# USB_UART.net
KiCad netlist of a schematic drawn in Altium Designer
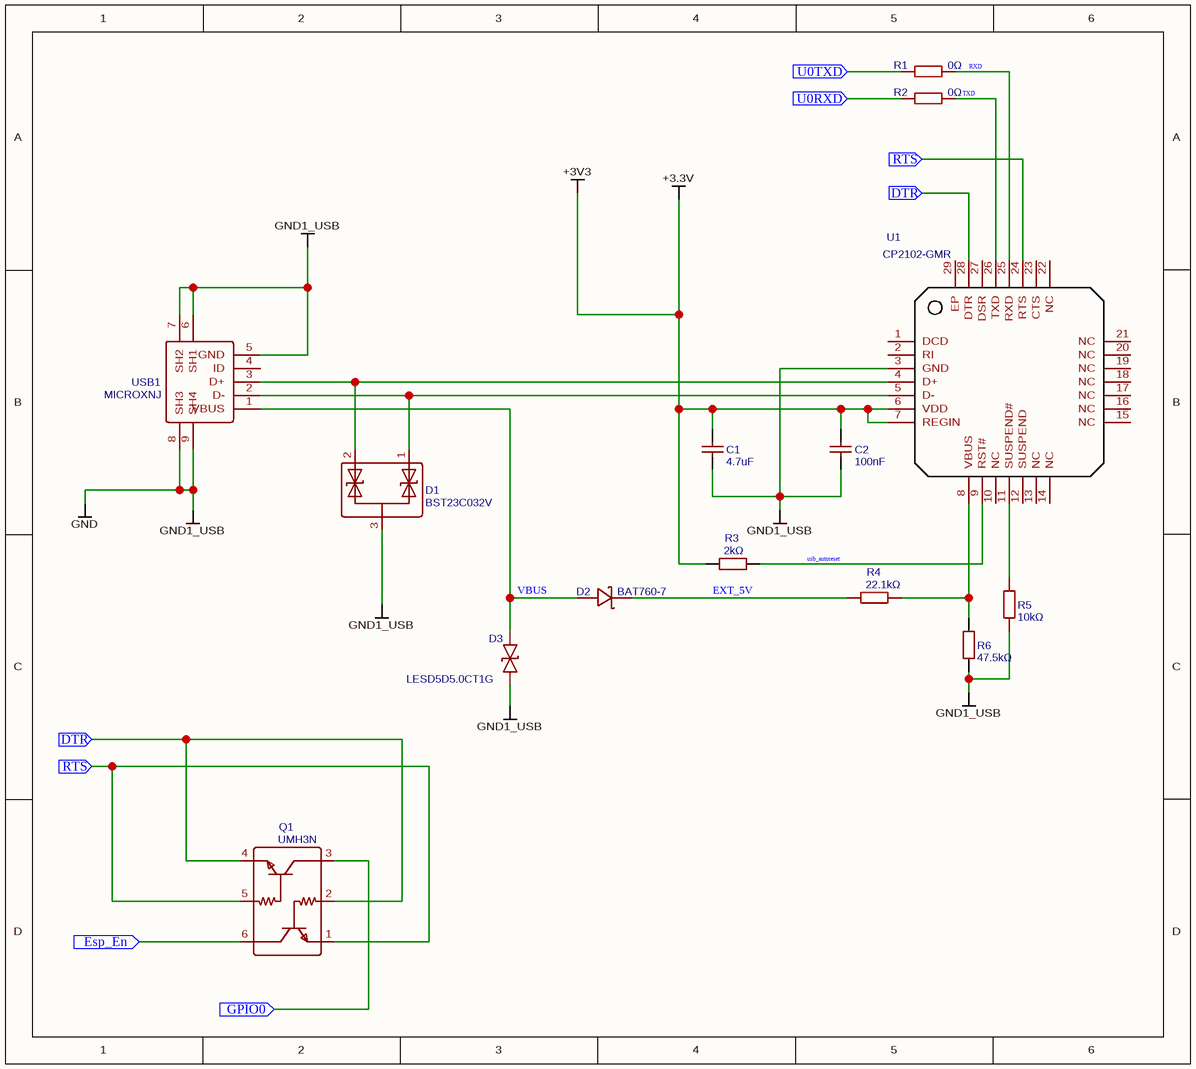
[diagram p0: USB_UART.schdoc]

(export (version "E")
  (design (tool "Eeschema 10.0.6"))
  (components
    (comp (ref "C1")
      (value "4.7uF")
      (fields
        (field (name "BOM_MANUFACTURER PART") "0603X475K160NT")
        (field (name "BOM_SUPPLIER PART") "C99229")
      )
      (libsource (lib "altium-import") (part "root_1_4.7uF_"))
    )
    (comp (ref "C2")
      (value "100nF")
      (fields
        (field (name "BOM_MANUFACTURER PART") "CL10B104KO8NNNC")
        (field (name "BOM_SUPPLIER PART") "C66501")
      )
      (libsource (lib "altium-import") (part "root_1_100nF_"))
    )
    (comp (ref "D1")
      (value "BST23C032V")
      (fields (field (name "BOM_SUPPLIER PART") "C151968") (field (name "CONTRIBUTOR") "LCSC"))
      (libsource (lib "altium-import") (part "root_2_BST23C032V_"))
    )
    (comp (ref "D2")
      (value "BAT760-7")
      (fields (field (name "BOM_SUPPLIER PART") "C124187") (field (name "CONTRIBUTOR") "LCSC"))
      (libsource (lib "altium-import") (part "root_2_BAT760-7_"))
    )
    (comp (ref "D3")
      (value "LESD5D5.0CT1G")
      (fields (field (name "BOM_SUPPLIER PART") "C383211") (field (name "CONTRIBUTOR") "LCSC"))
      (libsource (lib "altium-import") (part "root_1_LESD5D5.0CT1G_"))
    )
    (comp (ref "Q1")
      (value "UMH3N")
      (fields (field (name "BOM_SUPPLIER PART") "C62892"))
      (libsource (lib "altium-import") (part "root_1_UMH3N_"))
    )
    (comp (ref "R1")
      (value "0Ω")
      (fields
        (field (name "BOM_MANUFACTURER PART") "RS-03000FT")
        (field (name "BOM_SUPPLIER PART") "C136582")
        (field (name "CONTRIBUTOR") "LCSC")
      )
      (libsource (lib "altium-import") (part "root_0_0Ω_"))
    )
    (comp (ref "R2")
      (value "0Ω")
      (fields
        (field (name "BOM_MANUFACTURER PART") "RS-03000FT")
        (field (name "BOM_SUPPLIER PART") "C136582")
        (field (name "CONTRIBUTOR") "LCSC")
      )
      (libsource (lib "altium-import") (part "root_0_0Ω_"))
    )
    (comp (ref "R3")
      (value "2kΩ")
      (fields
        (field (name "BOM_MANUFACTURER PART") "RS-03K2001FT")
        (field (name "BOM_SUPPLIER PART") "C115336")
      )
      (libsource (lib "altium-import") (part "root_0_2kΩ_"))
    )
    (comp (ref "R4")
      (value "22.1kΩ")
      (fields
        (field (name "BOM_SUPPLIER PART") "C310274")
        (field (name "BOM_MANUFACTURER PART") "RS-03K2212FT")
        (field (name "CONTRIBUTOR") "LCSC")
      )
      (libsource (lib "altium-import") (part "root_0_22.1kΩ_"))
    )
    (comp (ref "R5")
      (value "10kΩ")
      (fields
        (field (name "BOM_SUPPLIER PART") "C115324")
        (field (name "BOM_MANUFACTURER PART") "RS-03K1002FT")
        (field (name "CONTRIBUTOR") "LCSC")
      )
      (libsource (lib "altium-import") (part "root_1_10kΩ_"))
    )
    (comp (ref "R6")
      (value "47.5kΩ")
      (fields
        (field (name "BOM_MANUFACTURER PART") "0603WAF4752T5E")
        (field (name "BOM_SUPPLIER PART") "C23061")
      )
      (libsource (lib "altium-import") (part "root_1_47.5kΩ_"))
    )
    (comp (ref "U1")
      (value "CP2102-GMR")
      (fields (field (name "BOM_SUPPLIER PART") "C6568"))
      (libsource (lib "altium-import") (part "root_0_CP2102-GMR_"))
    )
    (comp (ref "USB1")
      (value "MICROXNJ")
      (fields
        (field (name "BOM_SUPPLIER PART") "C404969")
        (field (name "BOM_MANUFACTURER PART") "MicroXNJ")
        (field (name "CONTRIBUTOR") "LCSC")
      )
      (libsource (lib "altium-import") (part "root_0_MICROXNJ_"))
    )
  )
  (nets
    (net (code "1") (name "+3.3V") (class "Default")
      (node (ref "C1") (pin "2") (pinfunction "2_2") (pintype "passive"))
      (node (ref "C2") (pin "2") (pinfunction "2_2") (pintype "passive"))
      (node (ref "R3") (pin "1") (pinfunction "1_1") (pintype "passive"))
      (node (ref "U1") (pin "6") (pinfunction "VDD_6") (pintype "passive"))
      (node (ref "U1") (pin "7") (pinfunction "REGIN_7") (pintype "passive"))
    )
    (net (code "2") (name "/DTR") (class "Default")
      (node (ref "Q1") (pin "2") (pinfunction "B_2") (pintype "passive"))
      (node (ref "Q1") (pin "4") (pinfunction "E_4") (pintype "passive"))
      (node (ref "U1") (pin "28") (pinfunction "DTR_28") (pintype "passive"))
    )
    (net (code "3") (name "/EXT_5V") (class "Default")
      (node (ref "D2") (pin "1") (pinfunction "1_1") (pintype "passive"))
      (node (ref "R4") (pin "1") (pinfunction "1_1") (pintype "passive"))
    )
    (net (code "4") (name "/Esp_En") (class "Default")
      (node (ref "Q1") (pin "6") (pinfunction "C_6") (pintype "passive"))
    )
    (net (code "5") (name "/GPIO0") (class "Default")
      (node (ref "Q1") (pin "3") (pinfunction "C_3") (pintype "passive"))
    )
    (net (code "6") (name "/RTS") (class "Default")
      (node (ref "Q1") (pin "1") (pinfunction "E_1") (pintype "passive"))
      (node (ref "Q1") (pin "5") (pinfunction "B_5") (pintype "passive"))
      (node (ref "U1") (pin "24") (pinfunction "RTS_24") (pintype "passive"))
    )
    (net (code "7") (name "/RXD") (class "Default")
      (node (ref "R1") (pin "2") (pinfunction "2_2") (pintype "passive"))
      (node (ref "U1") (pin "25") (pinfunction "RXD_25") (pintype "passive"))
    )
    (net (code "8") (name "/TXD") (class "Default")
      (node (ref "R2") (pin "2") (pinfunction "2_2") (pintype "passive"))
      (node (ref "U1") (pin "26") (pinfunction "TXD_26") (pintype "passive"))
    )
    (net (code "9") (name "/U0RXD") (class "Default")
      (node (ref "R2") (pin "1") (pinfunction "1_1") (pintype "passive"))
    )
    (net (code "10") (name "/U0TXD") (class "Default")
      (node (ref "R1") (pin "1") (pinfunction "1_1") (pintype "passive"))
    )
    (net (code "11") (name "/VBUS") (class "Default")
      (node (ref "D2") (pin "2") (pinfunction "2_2") (pintype "passive"))
      (node (ref "D3") (pin "2") (pinfunction "2_2") (pintype "passive"))
      (node (ref "USB1") (pin "1") (pinfunction "VBUS_1") (pintype "passive"))
    )
    (net (code "12") (name "/usb_autoreset") (class "Default")
      (node (ref "R3") (pin "2") (pinfunction "2_2") (pintype "passive"))
      (node (ref "U1") (pin "9") (pinfunction "RST#_9") (pintype "passive"))
    )
    (net (code "13") (name "GND") (class "Default")
      (node (ref "C1") (pin "1") (pinfunction "1_1") (pintype "passive"))
      (node (ref "C2") (pin "1") (pinfunction "1_1") (pintype "passive"))
      (node (ref "D1") (pin "3") (pinfunction "3_3") (pintype "passive"))
      (node (ref "D3") (pin "1") (pinfunction "1_1") (pintype "passive"))
      (node (ref "R5") (pin "1") (pinfunction "1_1") (pintype "passive"))
      (node (ref "R6") (pin "1") (pinfunction "1_1") (pintype "passive"))
      (node (ref "U1") (pin "3") (pinfunction "GND_3") (pintype "passive"))
      (node (ref "USB1") (pin "5") (pinfunction "GND_5") (pintype "passive"))
      (node (ref "USB1") (pin "6") (pinfunction "SH1_6") (pintype "passive"))
      (node (ref "USB1") (pin "7") (pinfunction "SH2_7") (pintype "passive"))
      (node (ref "USB1") (pin "8") (pinfunction "SH3_8") (pintype "passive"))
      (node (ref "USB1") (pin "9") (pinfunction "SH4_9") (pintype "passive"))
    )
    (net (code "14") (name "Net-(U1-D+)") (class "Default")
      (node (ref "D1") (pin "2") (pinfunction "2_2") (pintype "passive"))
      (node (ref "U1") (pin "4") (pinfunction "D+_4") (pintype "passive"))
      (node (ref "USB1") (pin "3") (pinfunction "D+_3") (pintype "passive"))
    )
    (net (code "15") (name "Net-(U1-D-)") (class "Default")
      (node (ref "D1") (pin "1") (pinfunction "1_1") (pintype "passive"))
      (node (ref "U1") (pin "5") (pinfunction "D-_5") (pintype "passive"))
      (node (ref "USB1") (pin "2") (pinfunction "D-_2") (pintype "passive"))
    )
    (net (code "16") (name "Net-(U1-SUSPEND#)") (class "Default")
      (node (ref "R5") (pin "2") (pinfunction "2_2") (pintype "passive"))
      (node (ref "U1") (pin "11") (pinfunction "SUSPEND#_11") (pintype "passive"))
    )
    (net (code "17") (name "Net-(U1-VBUS)") (class "Default")
      (node (ref "R4") (pin "2") (pinfunction "2_2") (pintype "passive"))
      (node (ref "R6") (pin "2") (pinfunction "2_2") (pintype "passive"))
      (node (ref "U1") (pin "8") (pinfunction "VBUS_8") (pintype "passive"))
    )
    (net (code "18") (name "unconnected-(U1-CTS-Pad23)") (class "Default")
      (node (ref "U1") (pin "23") (pinfunction "CTS_23") (pintype "passive"))
    )
    (net (code "19") (name "unconnected-(U1-DCD-Pad1)") (class "Default")
      (node (ref "U1") (pin "1") (pinfunction "DCD_1") (pintype "passive"))
    )
    (net (code "20") (name "unconnected-(U1-DSR-Pad27)") (class "Default")
      (node (ref "U1") (pin "27") (pinfunction "DSR_27") (pintype "passive"))
    )
    (net (code "21") (name "unconnected-(U1-EP-Pad29)") (class "Default")
      (node (ref "U1") (pin "29") (pinfunction "EP_29") (pintype "passive"))
    )
    (net (code "22") (name "unconnected-(U1-NC-Pad10)") (class "Default")
      (node (ref "U1") (pin "10") (pinfunction "NC_10") (pintype "passive"))
    )
    (net (code "23") (name "unconnected-(U1-NC-Pad13)") (class "Default")
      (node (ref "U1") (pin "13") (pinfunction "NC_13") (pintype "passive"))
    )
    (net (code "24") (name "unconnected-(U1-NC-Pad14)") (class "Default")
      (node (ref "U1") (pin "14") (pinfunction "NC_14") (pintype "passive"))
    )
    (net (code "25") (name "unconnected-(U1-NC-Pad15)") (class "Default")
      (node (ref "U1") (pin "15") (pinfunction "NC_15") (pintype "passive"))
    )
    (net (code "26") (name "unconnected-(U1-NC-Pad16)") (class "Default")
      (node (ref "U1") (pin "16") (pinfunction "NC_16") (pintype "passive"))
    )
    (net (code "27") (name "unconnected-(U1-NC-Pad17)") (class "Default")
      (node (ref "U1") (pin "17") (pinfunction "NC_17") (pintype "passive"))
    )
    (net (code "28") (name "unconnected-(U1-NC-Pad18)") (class "Default")
      (node (ref "U1") (pin "18") (pinfunction "NC_18") (pintype "passive"))
    )
    (net (code "29") (name "unconnected-(U1-NC-Pad19)") (class "Default")
      (node (ref "U1") (pin "19") (pinfunction "NC_19") (pintype "passive"))
    )
    (net (code "30") (name "unconnected-(U1-NC-Pad20)") (class "Default")
      (node (ref "U1") (pin "20") (pinfunction "NC_20") (pintype "passive"))
    )
    (net (code "31") (name "unconnected-(U1-NC-Pad21)") (class "Default")
      (node (ref "U1") (pin "21") (pinfunction "NC_21") (pintype "passive"))
    )
    (net (code "32") (name "unconnected-(U1-NC-Pad22)") (class "Default")
      (node (ref "U1") (pin "22") (pinfunction "NC_22") (pintype "passive"))
    )
    (net (code "33") (name "unconnected-(U1-RI-Pad2)") (class "Default")
      (node (ref "U1") (pin "2") (pinfunction "RI_2") (pintype "passive"))
    )
    (net (code "34") (name "unconnected-(U1-SUSPEND-Pad12)") (class "Default")
      (node (ref "U1") (pin "12") (pinfunction "SUSPEND_12") (pintype "passive"))
    )
    (net (code "35") (name "unconnected-(USB1-ID-Pad4)") (class "Default")
      (node (ref "USB1") (pin "4") (pinfunction "ID_4") (pintype "passive"))
    )
  )
)
